# Schematic.net
KiCad netlist of a schematic drawn in EAGLE
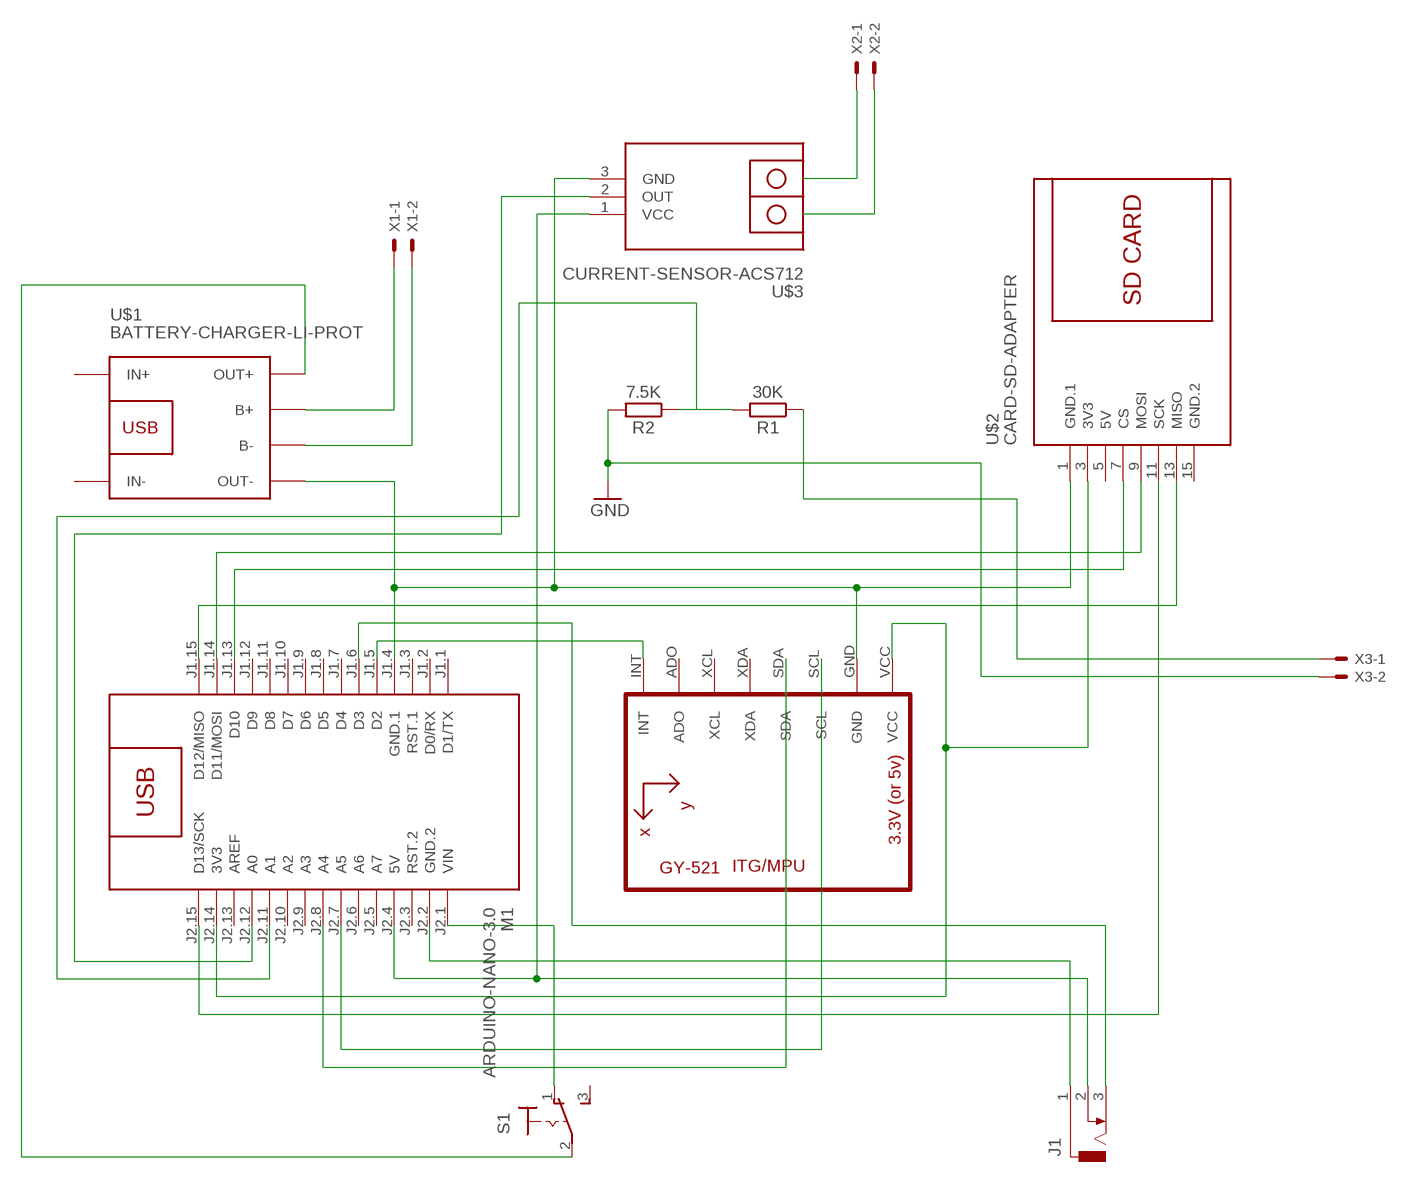
[diagram p0: schematic, sheet 1]

(export (version "E")
  (design (tool "Eeschema 10.0.6"))
  (components
    (comp (ref "J1")
      (value "DCJ0303")
      (footprint "eagle-import:DCJ0303")
      (libsource (lib "eagle-import") (part "DCJ0303"))
    )
    (comp (ref "M1")
      (value "ARDUINO-NANO-3.0")
      (footprint "eagle-import:ARDUINO-NANO-3.0")
      (libsource (lib "eagle-import") (part "ARDUINO-NANO-3.0"))
    )
    (comp (ref "R1")
      (value "30K")
      (footprint "eagle-import:RESAD724W46L381D178B")
      (libsource (lib "eagle-import") (part "RAXIAL-7.2MM-PITCH_"))
    )
    (comp (ref "R2")
      (value "7.5K")
      (footprint "eagle-import:RESAD724W46L381D178B")
      (libsource (lib "eagle-import") (part "RAXIAL-7.2MM-PITCH_"))
    )
    (comp (ref "S1")
      (value "320-916")
      (footprint "eagle-import:320-916")
      (libsource (lib "eagle-import") (part "320-916"))
    )
    (comp (ref "U$1")
      (value "BATTERY-CHARGER-LI-PROT")
      (footprint "eagle-import:BATTERY-CHARGER-LI-PROT")
      (libsource (lib "eagle-import") (part "BATTERY-CHARGER-LI-PROT"))
    )
    (comp (ref "U$2")
      (value "CARD-SD-ADAPTER")
      (footprint "eagle-import:CARD-SD-ADAPTER")
      (libsource (lib "eagle-import") (part "CARD-SD-ADAPTER"))
    )
    (comp (ref "U$3")
      (value "CURRENT-SENSOR-ACS712")
      (footprint "eagle-import:CURRENT-SENSOR-ACS712")
      (libsource (lib "eagle-import") (part "CURRENT-SENSOR-ACS712"))
    )
    (comp (ref "U1")
      (value "GY-521MPU6050")
      (footprint "eagle-import:GY-521")
      (libsource (lib "eagle-import") (part "GY-521MPU6050"))
    )
    (comp (ref "X1")
      (value "22-23-2021")
      (footprint "eagle-import:22-23-2021")
      (fields (field (name "MF") "MOLEX"))
      (libsource (lib "eagle-import") (part "22-23-2021"))
    )
    (comp (ref "X2")
      (value "22-23-2021")
      (footprint "eagle-import:22-23-2021")
      (fields (field (name "MF") "MOLEX"))
      (libsource (lib "eagle-import") (part "22-23-2021"))
    )
    (comp (ref "X3")
      (value "22-23-2021")
      (footprint "eagle-import:22-23-2021")
      (fields (field (name "MF") "MOLEX"))
      (libsource (lib "eagle-import") (part "22-23-2021"))
    )
  )
  (nets
    (net (code "1") (name "/5V") (class "Default")
      (node (ref "U$2") (pin "5") (pinfunction "5V_5") (pintype "power_in"))
    )
    (net (code "2") (name "/GND.2") (class "Default")
      (node (ref "U$2") (pin "15") (pinfunction "GND.2_15") (pintype "power_in"))
    )
    (net (code "3") (name "GND") (class "Default")
      (node (ref "R2") (pin "2") (pinfunction "2_2") (pintype "passive"))
      (node (ref "X3") (pin "2") (pinfunction "S_2") (pintype "passive"))
    )
    (net (code "4") (name "Net-(M1-3V3)") (class "Default")
      (node (ref "M1") (pin "J2.14") (pinfunction "3V3_J2.14") (pintype "power_in"))
      (node (ref "U$2") (pin "3") (pinfunction "3V3_3") (pintype "power_in"))
      (node (ref "U1") (pin "VCC") (pinfunction "VCC_VCC") (pintype "bidirectional"))
    )
    (net (code "5") (name "Net-(M1-5V)") (class "Default")
      (node (ref "J1") (pin "2") (pinfunction "2_2") (pintype "passive"))
      (node (ref "M1") (pin "J2.4") (pinfunction "5V_J2.4") (pintype "power_in"))
      (node (ref "U$3") (pin "1") (pinfunction "VCC_1") (pintype "power_in"))
    )
    (net (code "6") (name "Net-(M1-A0)") (class "Default")
      (node (ref "M1") (pin "J2.12") (pinfunction "A0_J2.12") (pintype "bidirectional"))
      (node (ref "U$3") (pin "2") (pinfunction "OUT_2") (pintype "output"))
    )
    (net (code "7") (name "Net-(M1-A1)") (class "Default")
      (node (ref "M1") (pin "J2.11") (pinfunction "A1_J2.11") (pintype "bidirectional"))
      (node (ref "R1") (pin "2") (pinfunction "2_2") (pintype "passive"))
      (node (ref "R2") (pin "1") (pinfunction "1_1") (pintype "passive"))
    )
    (net (code "8") (name "Net-(M1-A4)") (class "Default")
      (node (ref "M1") (pin "J2.8") (pinfunction "A4_J2.8") (pintype "bidirectional"))
      (node (ref "U1") (pin "SDA") (pinfunction "SDA_SDA") (pintype "bidirectional"))
    )
    (net (code "9") (name "Net-(M1-A5)") (class "Default")
      (node (ref "M1") (pin "J2.7") (pinfunction "A5_J2.7") (pintype "bidirectional"))
      (node (ref "U1") (pin "SCL") (pinfunction "SCL_SCL") (pintype "bidirectional"))
    )
    (net (code "10") (name "Net-(M1-D2)") (class "Default")
      (node (ref "M1") (pin "J1.5") (pinfunction "D2_J1.5") (pintype "bidirectional"))
      (node (ref "U1") (pin "INT") (pinfunction "INT_INT") (pintype "bidirectional"))
    )
    (net (code "11") (name "Net-(M1-D3)") (class "Default")
      (node (ref "J1") (pin "3") (pinfunction "3_3") (pintype "passive"))
      (node (ref "M1") (pin "J1.6") (pinfunction "D3_J1.6") (pintype "bidirectional"))
    )
    (net (code "12") (name "Net-(M1-D10)") (class "Default")
      (node (ref "M1") (pin "J1.13") (pinfunction "D10_J1.13") (pintype "bidirectional"))
      (node (ref "U$2") (pin "7") (pinfunction "CS_7") (pintype "bidirectional"))
    )
    (net (code "13") (name "Net-(M1-D11{slash}MOSI)") (class "Default")
      (node (ref "M1") (pin "J1.14") (pinfunction "D11/MOSI_J1.14") (pintype "bidirectional"))
      (node (ref "U$2") (pin "9") (pinfunction "MOSI_9") (pintype "bidirectional"))
    )
    (net (code "14") (name "Net-(M1-D12{slash}MISO)") (class "Default")
      (node (ref "M1") (pin "J1.15") (pinfunction "D12/MISO_J1.15") (pintype "bidirectional"))
      (node (ref "U$2") (pin "13") (pinfunction "MISO_13") (pintype "bidirectional"))
    )
    (net (code "15") (name "Net-(M1-D13{slash}SCK)") (class "Default")
      (node (ref "M1") (pin "J2.15") (pinfunction "D13/SCK_J2.15") (pintype "bidirectional"))
      (node (ref "U$2") (pin "11") (pinfunction "SCK_11") (pintype "bidirectional"))
    )
    (net (code "16") (name "Net-(M1-GND.1)") (class "Default")
      (node (ref "M1") (pin "J1.4") (pinfunction "GND.1_J1.4") (pintype "power_in"))
      (node (ref "U$1") (pin "OUT-") (pinfunction "OUT-_OUT-") (pintype "bidirectional"))
      (node (ref "U$2") (pin "1") (pinfunction "GND.1_1") (pintype "power_in"))
      (node (ref "U$3") (pin "3") (pinfunction "GND_3") (pintype "power_in"))
      (node (ref "U1") (pin "GND") (pinfunction "GND_GND") (pintype "bidirectional"))
    )
    (net (code "17") (name "Net-(M1-GND.2)") (class "Default")
      (node (ref "J1") (pin "1") (pinfunction "1_1") (pintype "passive"))
      (node (ref "M1") (pin "J2.2") (pinfunction "GND.2_J2.2") (pintype "power_in"))
    )
    (net (code "18") (name "Net-(M1-VIN)") (class "Default")
      (node (ref "M1") (pin "J2.1") (pinfunction "VIN_J2.1") (pintype "power_in"))
      (node (ref "S1") (pin "1") (pinfunction "O_1") (pintype "passive"))
    )
    (net (code "19") (name "Net-(S1-P)") (class "Default")
      (node (ref "S1") (pin "2") (pinfunction "P_2") (pintype "passive"))
      (node (ref "U$1") (pin "OUT+") (pinfunction "OUT+_OUT+") (pintype "bidirectional"))
    )
    (net (code "20") (name "Net-(X1A-S)") (class "Default")
      (node (ref "U$1") (pin "B+") (pinfunction "B+_B+") (pintype "bidirectional"))
      (node (ref "X1") (pin "1") (pinfunction "S_1") (pintype "passive"))
    )
    (net (code "21") (name "Net-(X1B-S)") (class "Default")
      (node (ref "U$1") (pin "B-") (pinfunction "B-_B-") (pintype "bidirectional"))
      (node (ref "X1") (pin "2") (pinfunction "S_2") (pintype "passive"))
    )
    (net (code "22") (name "Net-(X3A-S)") (class "Default")
      (node (ref "R1") (pin "1") (pinfunction "1_1") (pintype "passive"))
      (node (ref "X3") (pin "1") (pinfunction "S_1") (pintype "passive"))
    )
    (net (code "23") (name "unconnected-(M1-A2-PadJ2.10)") (class "Default")
      (node (ref "M1") (pin "J2.10") (pinfunction "A2_J2.10") (pintype "bidirectional"))
    )
    (net (code "24") (name "unconnected-(M1-A3-PadJ2.9)") (class "Default")
      (node (ref "M1") (pin "J2.9") (pinfunction "A3_J2.9") (pintype "bidirectional"))
    )
    (net (code "25") (name "unconnected-(M1-A6-PadJ2.6)") (class "Default")
      (node (ref "M1") (pin "J2.6") (pinfunction "A6_J2.6") (pintype "bidirectional"))
    )
    (net (code "26") (name "unconnected-(M1-A7-PadJ2.5)") (class "Default")
      (node (ref "M1") (pin "J2.5") (pinfunction "A7_J2.5") (pintype "bidirectional"))
    )
    (net (code "27") (name "unconnected-(M1-AREF-PadJ2.13)") (class "Default")
      (node (ref "M1") (pin "J2.13") (pinfunction "AREF_J2.13") (pintype "bidirectional"))
    )
    (net (code "28") (name "unconnected-(M1-D0{slash}RX-PadJ1.2)") (class "Default")
      (node (ref "M1") (pin "J1.2") (pinfunction "D0/RX_J1.2") (pintype "bidirectional"))
    )
    (net (code "29") (name "unconnected-(M1-D1{slash}TX-PadJ1.1)") (class "Default")
      (node (ref "M1") (pin "J1.1") (pinfunction "D1/TX_J1.1") (pintype "bidirectional"))
    )
    (net (code "30") (name "unconnected-(M1-D4-PadJ1.7)") (class "Default")
      (node (ref "M1") (pin "J1.7") (pinfunction "D4_J1.7") (pintype "bidirectional"))
    )
    (net (code "31") (name "unconnected-(M1-D5-PadJ1.8)") (class "Default")
      (node (ref "M1") (pin "J1.8") (pinfunction "D5_J1.8") (pintype "bidirectional"))
    )
    (net (code "32") (name "unconnected-(M1-D6-PadJ1.9)") (class "Default")
      (node (ref "M1") (pin "J1.9") (pinfunction "D6_J1.9") (pintype "bidirectional"))
    )
    (net (code "33") (name "unconnected-(M1-D7-PadJ1.10)") (class "Default")
      (node (ref "M1") (pin "J1.10") (pinfunction "D7_J1.10") (pintype "bidirectional"))
    )
    (net (code "34") (name "unconnected-(M1-D8-PadJ1.11)") (class "Default")
      (node (ref "M1") (pin "J1.11") (pinfunction "D8_J1.11") (pintype "bidirectional"))
    )
    (net (code "35") (name "unconnected-(M1-D9-PadJ1.12)") (class "Default")
      (node (ref "M1") (pin "J1.12") (pinfunction "D9_J1.12") (pintype "bidirectional"))
    )
    (net (code "36") (name "unconnected-(M1-RST.1-PadJ1.3)") (class "Default")
      (node (ref "M1") (pin "J1.3") (pinfunction "RST.1_J1.3") (pintype "bidirectional"))
    )
    (net (code "37") (name "unconnected-(M1-RST.2-PadJ2.3)") (class "Default")
      (node (ref "M1") (pin "J2.3") (pinfunction "RST.2_J2.3") (pintype "bidirectional"))
    )
    (net (code "38") (name "unconnected-(S1-S-Pad3)") (class "Default")
      (node (ref "S1") (pin "3") (pinfunction "S_3") (pintype "passive"))
    )
    (net (code "39") (name "unconnected-(U$1-PadIN+)") (class "Default")
      (node (ref "U$1") (pin "IN+") (pinfunction "IN+_IN+") (pintype "bidirectional"))
    )
    (net (code "40") (name "unconnected-(U$1-PadIN-)") (class "Default")
      (node (ref "U$1") (pin "IN-") (pinfunction "IN-_IN-") (pintype "bidirectional"))
    )
    (net (code "41") (name "unconnected-(U1-PadADO)") (class "Default")
      (node (ref "U1") (pin "ADO") (pinfunction "ADO_ADO") (pintype "bidirectional"))
    )
    (net (code "42") (name "unconnected-(U1-PadXCL)") (class "Default")
      (node (ref "U1") (pin "XCL") (pinfunction "XCL_XCL") (pintype "bidirectional"))
    )
    (net (code "43") (name "unconnected-(U1-PadXDA)") (class "Default")
      (node (ref "U1") (pin "XDA") (pinfunction "XDA_XDA") (pintype "bidirectional"))
    )
    (net (code "44") (name "unconnected-(X2A-S-Pad1)") (class "Default")
      (node (ref "X2") (pin "1") (pinfunction "S_1") (pintype "passive"))
    )
    (net (code "45") (name "unconnected-(X2B-S-Pad2)") (class "Default")
      (node (ref "X2") (pin "2") (pinfunction "S_2") (pintype "passive"))
    )
  )
)
